# MAIN.net
KiCad netlist of a schematic drawn in Altium Designer
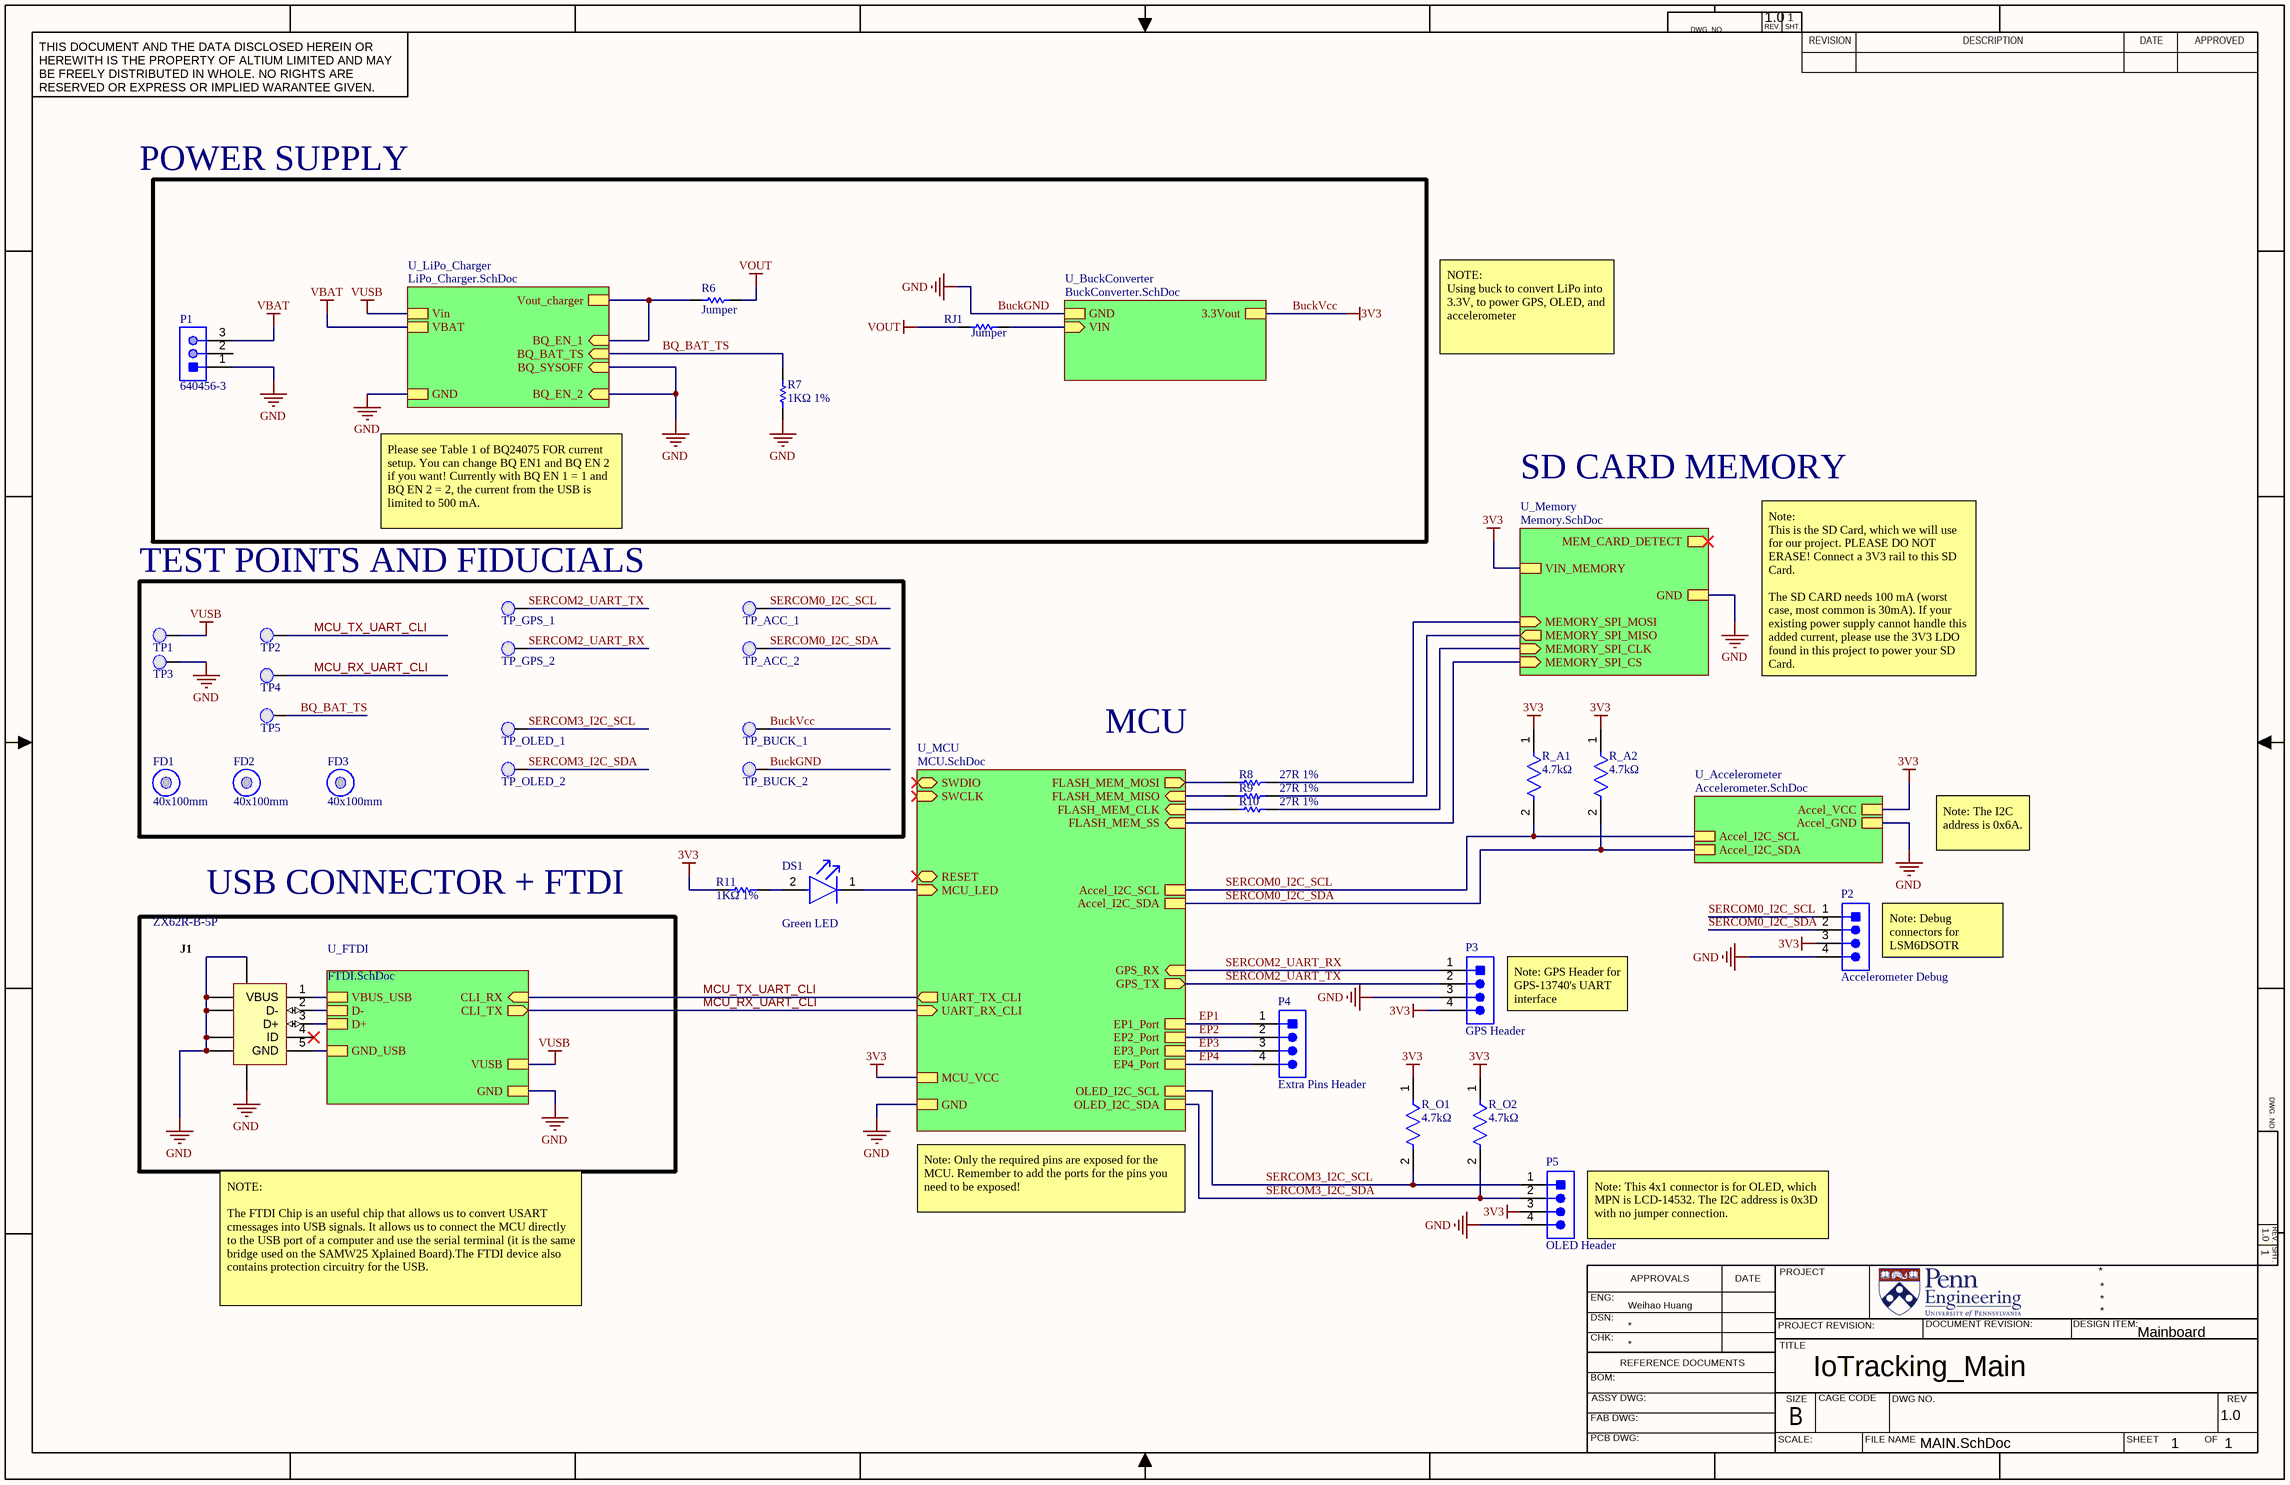
[diagram p0: MAIN.SchDoc]

(export (version "E")
  (design (tool "Eeschema 10.0.6"))
  (components
    (comp (ref "DS1")
      (value "Green LED")
      (footprint "FP-LTST-C191KGKT-MFG")
      (description "LED GREEN CLEAR SMD")
      (libsource (lib "Altium Content Vault") (part "8706943c75ba83719d021d2fdc84c58"))
    )
    (comp (ref "FD1")
      (value "40x100mm")
      (footprint "Fiducial_FT")
      (description "Fiducial 40x100mm")
      (libsource (lib "Components - 01.02.21 - 21.11") (part "CMP-00174-A.4"))
    )
    (comp (ref "FD2")
      (value "40x100mm")
      (footprint "Fiducial_FT")
      (description "Fiducial 40x100mm")
      (libsource (lib "Components - 01.02.21 - 21.11") (part "CMP-00174-A.4"))
    )
    (comp (ref "FD3")
      (value "40x100mm")
      (footprint "Fiducial_FT")
      (description "Fiducial 40x100mm")
      (libsource (lib "Components - 01.02.21 - 21.11") (part "CMP-00174-A.4"))
    )
    (comp (ref "J1")
      (value "ZX62R-B-5P")
      (footprint "HIRO-ZX62R-B-5P_V")
      (description "Connector; USBMicro-B,Reverse type, SMT; 5 Position; Right Angle")
      (libsource (lib "Altium Content Vault") (part "HIRO-ZX62R-B-5P-5"))
    )
    (comp (ref "P1")
      (value "640456-3")
      (footprint "TECO-640456-3")
      (description "Male Header, Pitch 2.54 mm, 1 x 3 Position, Height 10.03 mm, Tail Length 3.56 mm, -55 to 105 degC")
      (fields (field (name "MANUFACTURER") "TE Connectivity"))
      (libsource (lib "Altium Content Vault") (part "CN-1P-M-R3"))
    )
    (comp (ref "P2")
      (value "Accelerometer Debug")
      (footprint "TECO-640456-4")
      (description "Male Header, Pitch 2.54 mm, 1 x 4 Position, Height 10.03 mm, Tail Length 3.56 mm, RoHS, Bulk")
      (fields (field (name "MANUFACTURER") "TE Connectivity"))
      (libsource (lib "Altium Content Vault") (part "CN-1P-M-R4"))
    )
    (comp (ref "P3")
      (value "GPS Header")
      (footprint "TECO-640456-4")
      (description "Male Header, Pitch 2.54 mm, 1 x 4 Position, Height 10.03 mm, Tail Length 3.56 mm, RoHS, Bulk")
      (fields (field (name "MANUFACTURER") "TE Connectivity"))
      (libsource (lib "Altium Content Vault") (part "CN-1P-M-R4"))
    )
    (comp (ref "P4")
      (value "Extra Pins Header")
      (footprint "TECO-640456-4")
      (description "Male Header, Pitch 2.54 mm, 1 x 4 Position, Height 10.03 mm, Tail Length 3.56 mm, RoHS, Bulk")
      (fields (field (name "MANUFACTURER") "TE Connectivity"))
      (libsource (lib "Altium Content Vault") (part "CN-1P-M-R4"))
    )
    (comp (ref "P5")
      (value "OLED Header")
      (footprint "TECO-640456-4")
      (description "Male Header, Pitch 2.54 mm, 1 x 4 Position, Height 10.03 mm, Tail Length 3.56 mm, RoHS, Bulk")
      (fields (field (name "MANUFACTURER") "TE Connectivity"))
      (libsource (lib "Altium Content Vault") (part "CN-1P-M-R4"))
    )
    (comp (ref "R6")
      (value "Jumper")
      (footprint "RESC0805(2012)_N")
      (description "Jumper 0805 (2012 Metric)")
      (fields (field (name "TOLERANCE") "None"))
      (libsource (lib "Altium Content Vault") (part "RES"))
    )
    (comp (ref "R7")
      (value "1KΩ 1%")
      (footprint "RESC1609X50X30LL10T20")
      (description "1KΩ 1%CRCW06031K00FKEB")
      (fields (field (name "MANUFACTURER") "Vishay Dale") (field (name "PART NUMBER") "CRCW06031K00FKEB"))
      (libsource (lib "Altium Content Vault") (part "RES"))
    )
    (comp (ref "R8")
      (value "27R 1%")
      (footprint "RESC0603(1608)_N")
      (description "27R 0.1W 1% 0603 (1608 Metric)  SMD")
      (fields (field (name "TOLERANCE") "1 %") (field (name "POWER") "0.1 W"))
      (libsource (lib "Altium Content Vault") (part "RES"))
    )
    (comp (ref "R9")
      (value "27R 1%")
      (footprint "RESC0603(1608)_N")
      (description "27R 0.1W 1% 0603 (1608 Metric)  SMD")
      (fields (field (name "TOLERANCE") "1 %") (field (name "POWER") "0.1 W"))
      (libsource (lib "Altium Content Vault") (part "RES"))
    )
    (comp (ref "R10")
      (value "27R 1%")
      (footprint "RESC0603(1608)_N")
      (description "27R 0.1W 1% 0603 (1608 Metric)  SMD")
      (fields (field (name "TOLERANCE") "1 %") (field (name "POWER") "0.1 W"))
      (libsource (lib "Altium Content Vault") (part "RES"))
    )
    (comp (ref "R11")
      (value "1KΩ 1%")
      (footprint "RESC1609X50X30LL10T20")
      (description "1KΩ 1%CRCW06031K00FKEB")
      (fields (field (name "MANUFACTURER") "Vishay Dale") (field (name "PART NUMBER") "CRCW06031K00FKEB"))
      (libsource (lib "Altium Content Vault") (part "RES"))
    )
    (comp (ref "RJ1")
      (value "Jumper")
      (footprint "RESC1609X50X30LL10T20")
      (description "0 Ohm CRCW06030000Z0EC")
      (fields (field (name "MANUFACTURER") "Vishay Dale") (field (name "PART NUMBER") "CRCW06030000Z0EC"))
      (libsource (lib "Altium Content Vault") (part "RES"))
    )
    (comp (ref "R_A1")
      (value "4.7kΩ")
      (footprint "FP-AT0603-MFG")
      (description "RES SMD 4.7K OHM 0.5% 1/10W 0603")
      (fields (field (name "TOLERANCE") "0.005") (field (name "MANUFACTURER") "Yageo"))
      (libsource (lib "Altium Content Vault") (part "1029c3af85768c4190bb7ad29bc67b5"))
    )
    (comp (ref "R_A2")
      (value "4.7kΩ")
      (footprint "FP-AT0603-MFG")
      (description "RES SMD 4.7K OHM 0.5% 1/10W 0603")
      (fields (field (name "TOLERANCE") "0.005") (field (name "MANUFACTURER") "Yageo"))
      (libsource (lib "Altium Content Vault") (part "1029c3af85768c4190bb7ad29bc67b5"))
    )
    (comp (ref "R_O1")
      (value "4.7kΩ")
      (footprint "FP-AT0603-MFG")
      (description "RES SMD 4.7K OHM 0.5% 1/10W 0603")
      (fields (field (name "TOLERANCE") "0.005") (field (name "MANUFACTURER") "Yageo"))
      (libsource (lib "Altium Content Vault") (part "1029c3af85768c4190bb7ad29bc67b5"))
    )
    (comp (ref "R_O2")
      (value "4.7kΩ")
      (footprint "FP-AT0603-MFG")
      (description "RES SMD 4.7K OHM 0.5% 1/10W 0603")
      (fields (field (name "TOLERANCE") "0.005") (field (name "MANUFACTURER") "Yageo"))
      (libsource (lib "Altium Content Vault") (part "1029c3af85768c4190bb7ad29bc67b5"))
    )
    (comp (ref "TP1")
      (value "0.1\" Pad")
      (footprint "PCBComponent")
      (libsource (lib "Components - 12.02.20 - 18.05") (part "0.1{dblquote} Pad-A.4"))
    )
    (comp (ref "TP2")
      (value "0.1\" Pad")
      (footprint "PCBComponent")
      (libsource (lib "Components - 12.02.20 - 18.05") (part "0.1{dblquote} Pad-A.4"))
    )
    (comp (ref "TP3")
      (value "0.1\" Pad")
      (footprint "PCBComponent")
      (libsource (lib "Components - 12.02.20 - 18.05") (part "0.1{dblquote} Pad-A.4"))
    )
    (comp (ref "TP4")
      (value "0.1\" Pad")
      (footprint "PCBComponent")
      (libsource (lib "Components - 12.02.20 - 18.05") (part "0.1{dblquote} Pad-A.4"))
    )
    (comp (ref "TP5")
      (value "0.1\" Pad")
      (footprint "PCBComponent")
      (libsource (lib "Components - 12.02.20 - 18.05") (part "0.1{dblquote} Pad-A.4"))
    )
    (comp (ref "TP_ACC_1")
      (value "0.1\" Pad")
      (footprint "PCBComponent")
      (libsource (lib "Components - 12.02.20 - 18.05") (part "0.1{dblquote} Pad-A.4"))
    )
    (comp (ref "TP_ACC_2")
      (value "0.1\" Pad")
      (footprint "PCBComponent")
      (libsource (lib "Components - 12.02.20 - 18.05") (part "0.1{dblquote} Pad-A.4"))
    )
    (comp (ref "TP_BUCK_1")
      (value "0.1\" Pad")
      (footprint "PCBComponent")
      (libsource (lib "Components - 12.02.20 - 18.05") (part "0.1{dblquote} Pad-A.4"))
    )
    (comp (ref "TP_BUCK_2")
      (value "0.1\" Pad")
      (footprint "PCBComponent")
      (libsource (lib "Components - 12.02.20 - 18.05") (part "0.1{dblquote} Pad-A.4"))
    )
    (comp (ref "TP_GPS_1")
      (value "0.1\" Pad")
      (footprint "PCBComponent")
      (libsource (lib "Components - 12.02.20 - 18.05") (part "0.1{dblquote} Pad-A.4"))
    )
    (comp (ref "TP_GPS_2")
      (value "0.1\" Pad")
      (footprint "PCBComponent")
      (libsource (lib "Components - 12.02.20 - 18.05") (part "0.1{dblquote} Pad-A.4"))
    )
    (comp (ref "TP_OLED_1")
      (value "0.1\" Pad")
      (footprint "PCBComponent")
      (libsource (lib "Components - 12.02.20 - 18.05") (part "0.1{dblquote} Pad-A.4"))
    )
    (comp (ref "TP_OLED_2")
      (value "0.1\" Pad")
      (footprint "PCBComponent")
      (libsource (lib "Components - 12.02.20 - 18.05") (part "0.1{dblquote} Pad-A.4"))
    )
  )
  (nets
    (net (code "1") (name "/BQ_BAT_TS") (class "Default")
      (node (ref "R7") (pin "1") (pinfunction "1_1") (pintype "passive"))
      (node (ref "TP5") (pin "1") (pinfunction "PAD_1") (pintype "passive"))
    )
    (net (code "2") (name "/BQ_EN_1") (class "Default")
      (node (ref "R6") (pin "1") (pinfunction "1_1") (pintype "passive"))
    )
    (net (code "3") (name "/D+") (class "Default")
      (node (ref "J1") (pin "3") (pinfunction "D+_3") (pintype "bidirectional"))
    )
    (net (code "4") (name "/D-") (class "Default")
      (node (ref "J1") (pin "2") (pinfunction "D-_2") (pintype "bidirectional"))
    )
    (net (code "5") (name "/EP1") (class "Default")
      (node (ref "P4") (pin "1") (pinfunction "1_1") (pintype "passive"))
    )
    (net (code "6") (name "/EP2") (class "Default")
      (node (ref "P4") (pin "2") (pinfunction "2_2") (pintype "passive"))
    )
    (net (code "7") (name "/EP3") (class "Default")
      (node (ref "P4") (pin "3") (pinfunction "3_3") (pintype "passive"))
    )
    (net (code "8") (name "/EP4") (class "Default")
      (node (ref "P4") (pin "4") (pinfunction "4_4") (pintype "passive"))
    )
    (net (code "9") (name "/FLASH_MEM_CLK") (class "Default")
      (node (ref "R10") (pin "1") (pinfunction "1_1") (pintype "passive"))
    )
    (net (code "10") (name "/FLASH_MEM_MISO") (class "Default")
      (node (ref "R9") (pin "1") (pinfunction "1_1") (pintype "passive"))
    )
    (net (code "11") (name "/FLASH_MEM_MOSI") (class "Default")
      (node (ref "R8") (pin "1") (pinfunction "1_1") (pintype "passive"))
    )
    (net (code "13") (name "/GND_USB") (class "Default")
      (node (ref "J1") (pin "5") (pinfunction "GND_5") (pintype "power_in"))
    )
    (net (code "14") (name "/MCU_LED") (class "Default")
      (node (ref "DS1") (pin "1") (pinfunction "C_1") (pintype "passive"))
    )
    (net (code "15") (name "/MCU_RX_UART_CLI") (class "Default")
      (node (ref "TP4") (pin "1") (pinfunction "PAD_1") (pintype "passive"))
    )
    (net (code "16") (name "/MCU_TX_UART_CLI") (class "Default")
      (node (ref "TP2") (pin "1") (pinfunction "PAD_1") (pintype "passive"))
    )
    (net (code "17") (name "/MEMORY_SPI_CLK") (class "Default")
      (node (ref "R10") (pin "2") (pinfunction "2_2") (pintype "passive"))
    )
    (net (code "18") (name "/MEMORY_SPI_MISO") (class "Default")
      (node (ref "R9") (pin "2") (pinfunction "2_2") (pintype "passive"))
    )
    (net (code "19") (name "/MEMORY_SPI_MOSI") (class "Default")
      (node (ref "R8") (pin "2") (pinfunction "2_2") (pintype "passive"))
    )
    (net (code "22") (name "/SERCOM0_I2C_SCL") (class "Default")
      (node (ref "P2") (pin "1") (pinfunction "1_1") (pintype "passive"))
      (node (ref "R_A1") (pin "2") (pinfunction "2_2") (pintype "passive"))
      (node (ref "TP_ACC_1") (pin "1") (pinfunction "PAD_1") (pintype "passive"))
    )
    (net (code "23") (name "/SERCOM0_I2C_SDA") (class "Default")
      (node (ref "P2") (pin "2") (pinfunction "2_2") (pintype "passive"))
      (node (ref "R_A2") (pin "2") (pinfunction "2_2") (pintype "passive"))
      (node (ref "TP_ACC_2") (pin "1") (pinfunction "PAD_1") (pintype "passive"))
    )
    (net (code "24") (name "/SERCOM2_UART_RX") (class "Default")
      (node (ref "P3") (pin "1") (pinfunction "1_1") (pintype "passive"))
      (node (ref "TP_GPS_2") (pin "1") (pinfunction "PAD_1") (pintype "passive"))
    )
    (net (code "25") (name "/SERCOM2_UART_TX") (class "Default")
      (node (ref "P3") (pin "2") (pinfunction "2_2") (pintype "passive"))
      (node (ref "TP_GPS_1") (pin "1") (pinfunction "PAD_1") (pintype "passive"))
    )
    (net (code "26") (name "/SERCOM3_I2C_SCL") (class "Default")
      (node (ref "P5") (pin "1") (pinfunction "1_1") (pintype "passive"))
      (node (ref "R_O1") (pin "2") (pinfunction "2_2") (pintype "passive"))
      (node (ref "TP_OLED_1") (pin "1") (pinfunction "PAD_1") (pintype "passive"))
    )
    (net (code "27") (name "/SERCOM3_I2C_SDA") (class "Default")
      (node (ref "P5") (pin "2") (pinfunction "2_2") (pintype "passive"))
      (node (ref "R_O2") (pin "2") (pinfunction "2_2") (pintype "passive"))
      (node (ref "TP_OLED_2") (pin "1") (pinfunction "PAD_1") (pintype "passive"))
    )
    (net (code "30") (name "/VBUS_USB") (class "Default")
      (node (ref "J1") (pin "1") (pinfunction "VBUS_1") (pintype "power_in"))
    )
    (net (code "31") (name "/VIN") (class "Default")
      (node (ref "RJ1") (pin "2") (pinfunction "2_2") (pintype "passive"))
    )
    (net (code "32") (name "3V3") (class "Default")
      (node (ref "P2") (pin "3") (pinfunction "3_3") (pintype "passive"))
      (node (ref "P3") (pin "4") (pinfunction "4_4") (pintype "passive"))
      (node (ref "P5") (pin "3") (pinfunction "3_3") (pintype "passive"))
      (node (ref "R11") (pin "1") (pinfunction "1_1") (pintype "passive"))
      (node (ref "R_A1") (pin "1") (pinfunction "1_1") (pintype "passive"))
      (node (ref "R_A2") (pin "1") (pinfunction "1_1") (pintype "passive"))
      (node (ref "R_O1") (pin "1") (pinfunction "1_1") (pintype "passive"))
      (node (ref "R_O2") (pin "1") (pinfunction "1_1") (pintype "passive"))
      (node (ref "TP_BUCK_1") (pin "1") (pinfunction "PAD_1") (pintype "passive"))
    )
    (net (code "33") (name "GND") (class "Default")
      (node (ref "J1") (pin "10") (pinfunction "SHLD_10") (pintype "passive"))
      (node (ref "J1") (pin "11") (pinfunction "SHLD_11") (pintype "passive"))
      (node (ref "J1") (pin "6") (pinfunction "SHLD_6") (pintype "passive"))
      (node (ref "J1") (pin "7") (pinfunction "SHLD_7") (pintype "passive"))
      (node (ref "J1") (pin "8") (pinfunction "SHLD_8") (pintype "passive"))
      (node (ref "J1") (pin "9") (pinfunction "SHLD_9") (pintype "passive"))
      (node (ref "P1") (pin "1") (pinfunction "1_1") (pintype "passive"))
      (node (ref "P2") (pin "4") (pinfunction "4_4") (pintype "passive"))
      (node (ref "P3") (pin "3") (pinfunction "3_3") (pintype "passive"))
      (node (ref "P5") (pin "4") (pinfunction "4_4") (pintype "passive"))
      (node (ref "R7") (pin "2") (pinfunction "2_2") (pintype "passive"))
      (node (ref "TP3") (pin "1") (pinfunction "PAD_1") (pintype "passive"))
      (node (ref "TP_BUCK_2") (pin "1") (pinfunction "PAD_1") (pintype "passive"))
    )
    (net (code "34") (name "Net-(DS1-A)") (class "Default")
      (node (ref "DS1") (pin "2") (pinfunction "A_2") (pintype "passive"))
      (node (ref "R11") (pin "2") (pinfunction "2_2") (pintype "passive"))
    )
    (net (code "35") (name "VBAT") (class "Default")
      (node (ref "P1") (pin "3") (pinfunction "3_3") (pintype "passive"))
    )
    (net (code "36") (name "VOUT") (class "Default")
      (node (ref "R6") (pin "2") (pinfunction "2_2") (pintype "passive"))
      (node (ref "RJ1") (pin "1") (pinfunction "1_1") (pintype "passive"))
    )
    (net (code "37") (name "VUSB") (class "Default")
      (node (ref "TP1") (pin "1") (pinfunction "PAD_1") (pintype "passive"))
    )
    (net (code "38") (name "unconnected-(J1-ID-Pad4)") (class "Default")
      (node (ref "J1") (pin "4") (pinfunction "ID_4") (pintype "passive+no_connect"))
    )
    (net (code "39") (name "unconnected-(P1-Pad2)") (class "Default")
      (node (ref "P1") (pin "2") (pinfunction "2_2") (pintype "passive"))
    )
  )
)
